# USB.net
KiCad netlist of a schematic drawn in Altium Designer
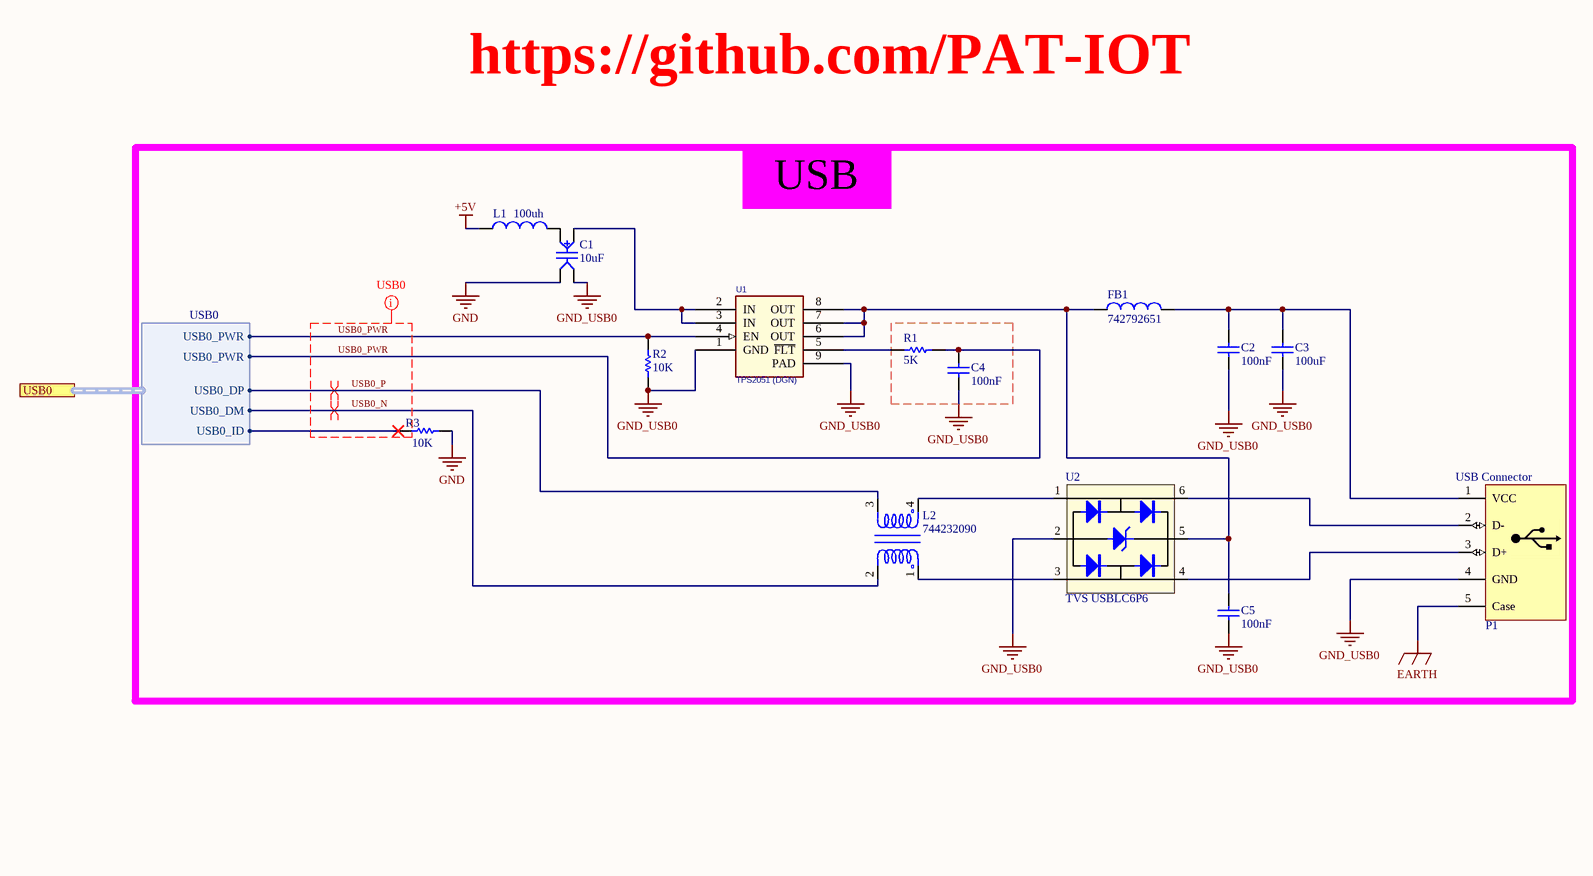
[diagram p0: USB.SchDoc]

(export (version "E")
  (design (tool "Eeschema 10.0.6"))
  (components
    (comp (ref "C1")
      (value "10uF")
      (footprint "CAP0805 - Low Noise")
      (description "Capacitor Ceramic")
      (fields (field (name "0-DESIGNER") "Telegram: @PATARM"))
      (libsource (lib "PAT_Schematic") (part "Capacitor Low Noise"))
    )
    (comp (ref "C2")
      (value "100nF")
      (footprint "CAP0805")
      (description "Capacitor SMD")
      (fields (field (name "DESIGNER") "Abbas Basereh"))
      (libsource (lib "PAT_Schematic") (part "Capacitor SMD"))
    )
    (comp (ref "C3")
      (value "100uF")
      (footprint "CAP0805")
      (description "Capacitor SMD")
      (fields (field (name "DESIGNER") "Abbas Basereh"))
      (libsource (lib "PAT_Schematic") (part "Capacitor SMD"))
    )
    (comp (ref "C4")
      (value "100nF")
      (footprint "CAP0805")
      (description "Capacitor SMD")
      (fields (field (name "DESIGNER") "Abbas Basereh"))
      (libsource (lib "PAT_Schematic") (part "Capacitor SMD"))
    )
    (comp (ref "C5")
      (value "100nF")
      (footprint "CAP0805")
      (description "Capacitor SMD")
      (fields (field (name "DESIGNER") "Abbas Basereh"))
      (libsource (lib "PAT_Schematic") (part "Capacitor SMD"))
    )
    (comp (ref "FB1")
      (value "742792651")
      (footprint "FB0603")
      (description "600 Ohms @ 100MHz 1 Signal Line Ferrite Bead 0603 (1608 Metric) 1A 200mOhm")
      (fields (field (name "MF") "Wurth Electronics"))
      (libsource (lib "742792651") (part "742792651"))
    )
    (comp (ref "L1")
      (value "100uh")
      (footprint "IND0805")
      (description "TOTAL INDUCTOR SMD PACK")
      (fields (field (name "DESIGNER") "Abbas Basereh"))
      (libsource (lib "PAT_Schematic") (part "INDUCTOR SMD PACKAGE"))
    )
    (comp (ref "L2")
      (value "744232090")
      (footprint "IND_744232090")
      (description "2 Line Common Mode Choke Surface Mount 90 Ohms @ 100MHz 370mA DCR 300mOhm")
      (fields (field (name "DIGI-KEY_PART_NUMBER") "732-1469-1-ND") (field (name "MF") "Wurth Electronics"))
      (libsource (lib "744232090") (part "744232090"))
    )
    (comp (ref "P1")
      (value "USB Connector")
      (footprint "USB2.5-2H4C Flash")
      (description "USB Connector-A Type")
      (libsource (lib "USB") (part "USB A-Type case"))
    )
    (comp (ref "R1")
      (value "5K")
      (footprint "RES0603")
      (description "Resistor")
      (libsource (lib "PAT_Schematic") (part "Resistor"))
    )
    (comp (ref "R2")
      (value "10K")
      (footprint "RES0603")
      (description "Resistor")
      (libsource (lib "PAT_Schematic") (part "Resistor"))
    )
    (comp (ref "R3")
      (value "10K")
      (footprint "RES0603_(1608X06L)")
      (description "Resistor")
      (libsource (lib "PAT_Schematic") (part "Resistor"))
    )
    (comp (ref "U1")
      (value "TPS2051 (DGN)")
      (footprint "*SOP65P490X110-9N_PMIC-TPS2051BDGN(MSOP8)(Primary)")
      (description "IC 1.5A PWR DIST SWITCH 8-SOIC")
      (fields
        (field (name "MANUFACTURER") "Texas Instruments")
        (field (name "MANUFACTURER PART NUMBER") "TPS2051BDGNR")
      )
      (libsource (lib "BEAGLEBONEBLACK_REV A5B") (part "TPS2061_0"))
    )
    (comp (ref "U2")
      (value "TVS USBLC6P6")
      (footprint "TI SOT-23-6 DBV")
      (description "HIGH DENSITY MOUNTING PHOTOTRANSISTOR OPTICALLY COUPLED ISOLATORS")
      (fields (field (name "CREATOR") "Saeid Jorablo"))
      (libsource (lib "PAT_Schematic") (part "TVS USBLC6P6"))
    )
  )
  (nets
    (net (code "2") (name "+5V") (class "Default")
      (node (ref "L1") (pin "1") (pinfunction "1_1") (pintype "passive"))
    )
    (net (code "3") (name "/USB0_ID") (class "Default")
      (node (ref "R3") (pin "2") (pinfunction "2_2") (pintype "passive+no_connect"))
    )
    (net (code "4") (name "/USB0_N") (class "Default")
      (node (ref "L2") (pin "2") (pinfunction "2_2") (pintype "passive"))
    )
    (net (code "5") (name "/USB0_P") (class "Default")
      (node (ref "L2") (pin "3") (pinfunction "3_3") (pintype "passive"))
    )
    (net (code "6") (name "/USB0_PWR") (class "Default")
      (node (ref "C4") (pin "2") (pinfunction "2_2") (pintype "passive"))
      (node (ref "R1") (pin "2") (pinfunction "2_2") (pintype "passive"))
      (node (ref "R2") (pin "1") (pinfunction "1_1") (pintype "passive"))
      (node (ref "U1") (pin "4") (pinfunction "EN_4") (pintype "input"))
    )
    (net (code "8") (name "EARTH") (class "Default")
      (node (ref "P1") (pin "5") (pinfunction "Case_5") (pintype "power_in"))
    )
    (net (code "9") (name "GND") (class "Default")
      (node (ref "C1") (pin "4") (pinfunction "4_4") (pintype "passive"))
      (node (ref "R3") (pin "1") (pinfunction "1_1") (pintype "passive"))
    )
    (net (code "10") (name "GND_USB0") (class "Default")
      (node (ref "C1") (pin "2") (pinfunction "2_2") (pintype "passive"))
      (node (ref "C2") (pin "1") (pinfunction "1_1") (pintype "passive"))
      (node (ref "C3") (pin "1") (pinfunction "1_1") (pintype "passive"))
      (node (ref "C4") (pin "1") (pinfunction "1_1") (pintype "passive"))
      (node (ref "C5") (pin "1") (pinfunction "1_1") (pintype "passive"))
      (node (ref "P1") (pin "4") (pinfunction "GND_4") (pintype "power_in"))
      (node (ref "R2") (pin "2") (pinfunction "2_2") (pintype "passive"))
      (node (ref "U1") (pin "1") (pinfunction "GND_1") (pintype "power_in"))
      (node (ref "U1") (pin "9") (pinfunction "PAD_9") (pintype "passive"))
      (node (ref "U2") (pin "2") (pinfunction "GND_2") (pintype "passive"))
    )
    (net (code "11") (name "Net-(C1-Pad1)") (class "Default")
      (node (ref "C1") (pin "1") (pinfunction "1_1") (pintype "passive"))
      (node (ref "U1") (pin "2") (pinfunction "IN_2") (pintype "power_in"))
      (node (ref "U1") (pin "3") (pinfunction "IN_3") (pintype "power_in"))
    )
    (net (code "12") (name "Net-(C1-Pad3)") (class "Default")
      (node (ref "C1") (pin "3") (pinfunction "3_3") (pintype "passive"))
      (node (ref "L1") (pin "2") (pinfunction "2_2") (pintype "passive"))
    )
    (net (code "13") (name "Net-(P1-D+)") (class "Default")
      (node (ref "P1") (pin "3") (pinfunction "D+_3") (pintype "bidirectional"))
      (node (ref "U2") (pin "4") (pinfunction "OUT2_4") (pintype "passive"))
    )
    (net (code "14") (name "Net-(P1-D-)") (class "Default")
      (node (ref "P1") (pin "2") (pinfunction "D-_2") (pintype "bidirectional"))
      (node (ref "U2") (pin "6") (pinfunction "OUT1_6") (pintype "passive"))
    )
    (net (code "15") (name "Net-(P1-VCC)") (class "Default")
      (node (ref "C2") (pin "2") (pinfunction "2_2") (pintype "passive"))
      (node (ref "C3") (pin "2") (pinfunction "2_2") (pintype "passive"))
      (node (ref "FB1") (pin "2") (pinfunction "2_2") (pintype "passive"))
      (node (ref "P1") (pin "1") (pinfunction "VCC_1") (pintype "power_in"))
    )
    (net (code "16") (name "Net-(U1-~{FLT})") (class "Default")
      (node (ref "R1") (pin "1") (pinfunction "1_1") (pintype "passive"))
      (node (ref "U1") (pin "5") (pinfunction "~{FLT}_5") (pintype "open_collector"))
    )
    (net (code "17") (name "Net-(U2-IN1)") (class "Default")
      (node (ref "L2") (pin "4") (pinfunction "4_4") (pintype "passive"))
      (node (ref "U2") (pin "1") (pinfunction "IN1_1") (pintype "passive"))
    )
    (net (code "18") (name "Net-(U2-IN2)") (class "Default")
      (node (ref "L2") (pin "1") (pinfunction "1_1") (pintype "passive"))
      (node (ref "U2") (pin "3") (pinfunction "IN2_3") (pintype "passive"))
    )
    (net (code "19") (name "Net-(U2-VCC)") (class "Default")
      (node (ref "C5") (pin "2") (pinfunction "2_2") (pintype "passive"))
      (node (ref "FB1") (pin "1") (pinfunction "1_1") (pintype "passive"))
      (node (ref "U1") (pin "6") (pinfunction "OUT_6") (pintype "power_in"))
      (node (ref "U1") (pin "7") (pinfunction "OUT_7") (pintype "power_in"))
      (node (ref "U1") (pin "8") (pinfunction "OUT_8") (pintype "power_in"))
      (node (ref "U2") (pin "5") (pinfunction "VCC_5") (pintype "passive"))
    )
  )
)
